# Sheet2.net
KiCad netlist of a schematic drawn in Altium Designer
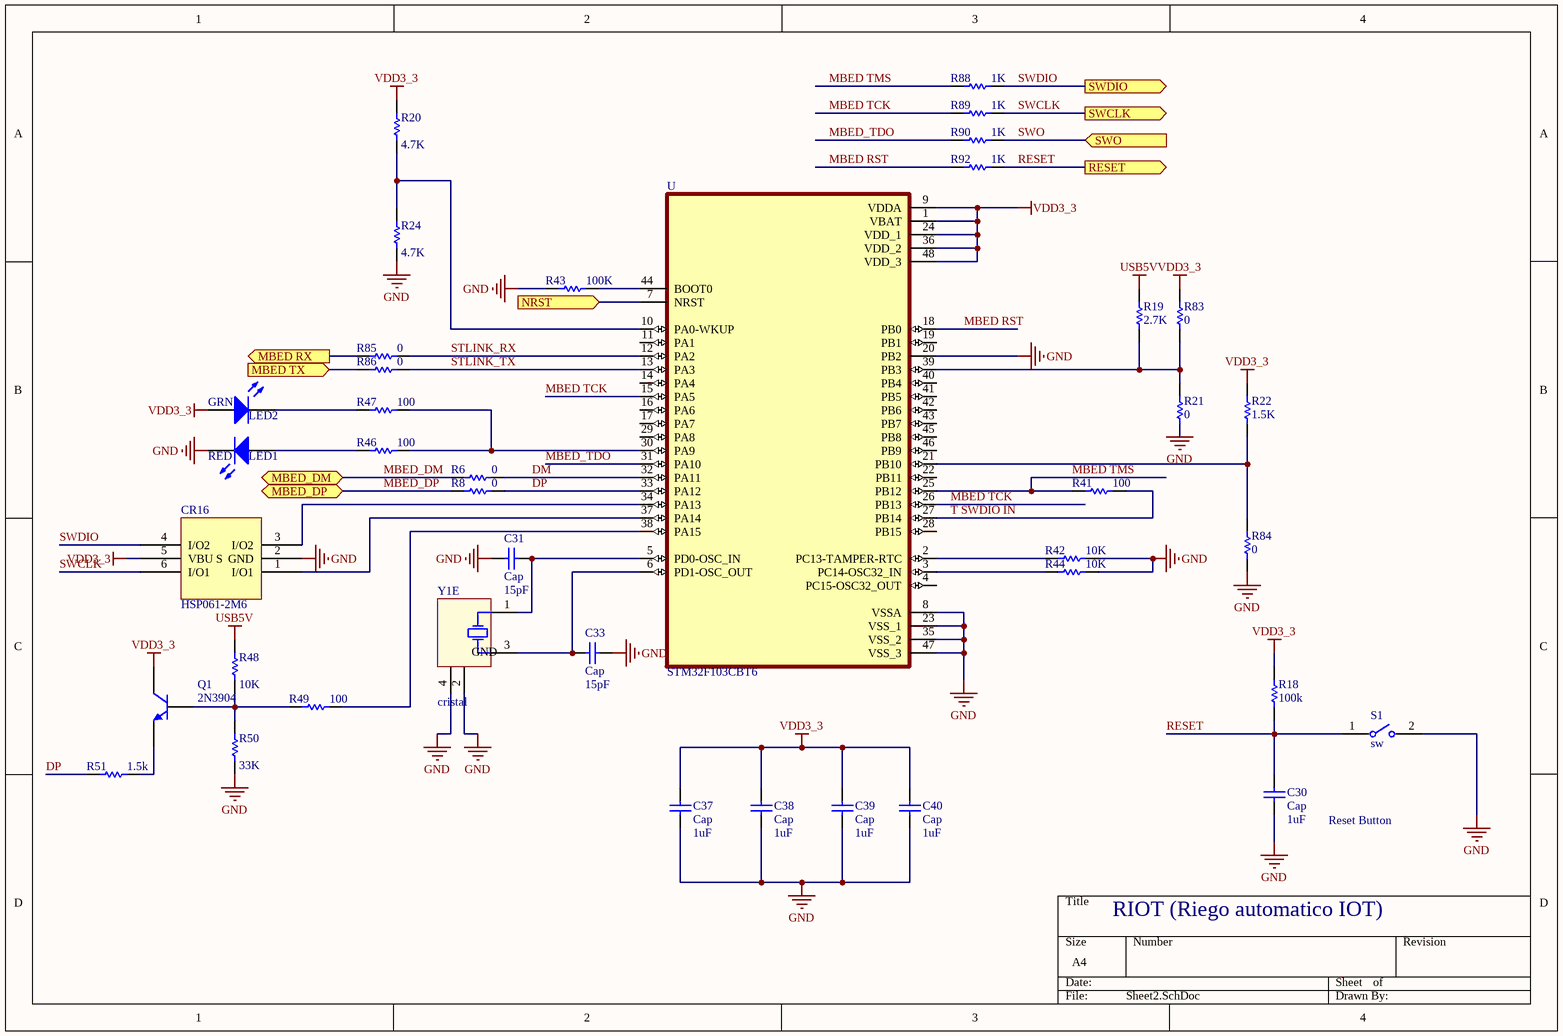
[diagram p0: Sheet2.SchDoc]

(export (version "E")
  (design (tool "Eeschema 10.0.6"))
  (components
    (comp (ref "C30")
      (value "Cap")
      (footprint "CAPC1005X35N")
      (description "Capacitor")
      (fields (field (name "ALTIUM_VALUE") "1uF") (field (name "PUBLISHER") "Altium Limited"))
      (libsource (lib "Miscellaneous Devices") (part "Cap"))
    )
    (comp (ref "C31")
      (value "Cap")
      (footprint "CAPC1005X35N")
      (description "Capacitor")
      (fields (field (name "ALTIUM_VALUE") "15pF") (field (name "PUBLISHER") "Altium Limited"))
      (libsource (lib "Miscellaneous Devices") (part "Cap"))
    )
    (comp (ref "C33")
      (value "Cap")
      (footprint "CAPC1005X35N")
      (description "Capacitor")
      (fields (field (name "ALTIUM_VALUE") "15pF") (field (name "PUBLISHER") "Altium Limited"))
      (libsource (lib "Miscellaneous Devices") (part "Cap"))
    )
    (comp (ref "C37")
      (value "Cap")
      (footprint "CAPC1005X35N")
      (description "Capacitor")
      (fields (field (name "ALTIUM_VALUE") "1uF") (field (name "PUBLISHER") "Altium Limited"))
      (libsource (lib "Miscellaneous Devices") (part "Cap"))
    )
    (comp (ref "C38")
      (value "Cap")
      (footprint "CAPC1005X35N")
      (description "Capacitor")
      (fields (field (name "ALTIUM_VALUE") "1uF") (field (name "PUBLISHER") "Altium Limited"))
      (libsource (lib "Miscellaneous Devices") (part "Cap"))
    )
    (comp (ref "C39")
      (value "Cap")
      (footprint "CAPC1005X35N")
      (description "Capacitor")
      (fields (field (name "ALTIUM_VALUE") "1uF") (field (name "PUBLISHER") "Altium Limited"))
      (libsource (lib "Miscellaneous Devices") (part "Cap"))
    )
    (comp (ref "C40")
      (value "Cap")
      (footprint "CAPC1005X35N")
      (description "Capacitor")
      (fields (field (name "ALTIUM_VALUE") "1uF") (field (name "PUBLISHER") "Altium Limited"))
      (libsource (lib "Miscellaneous Devices") (part "Cap"))
    )
    (comp (ref "CR16")
      (value "HSP061-2M6")
      (footprint "PSON40P120X130X55-6N")
      (libsource (lib "Components - 07.03.22 - 14.02") (part "HSP061-2M6"))
    )
    (comp (ref "GRN")
      (value "LED2")
      (footprint "FP-SML-P11MTT86-MFG")
      (description "Typical INFRARED GaAs LED")
      (fields (field (name "PUBLISHER") "Altium Limited"))
      (libsource (lib "Miscellaneous Devices") (part "LED0"))
    )
    (comp (ref "Q1")
      (value "2N3904")
      (footprint "TO-92A")
      (description "NPN General Purpose Amplifier")
      (fields (field (name "PUBLISHER") "Altium Limited"))
      (libsource (lib "Miscellaneous Devices") (part "2N3904"))
    )
    (comp (ref "R6")
      (value "0")
      (footprint "RESC1005X35N")
      (description "Resistor")
      (fields (field (name "Comment") "Res1") (field (name "PUBLISHER") "Altium Limited"))
      (libsource (lib "Miscellaneous Devices") (part "Res1"))
    )
    (comp (ref "R8")
      (value "0")
      (footprint "RESC1005X35N")
      (description "Resistor")
      (fields (field (name "Comment") "Res1") (field (name "PUBLISHER") "Altium Limited"))
      (libsource (lib "Miscellaneous Devices") (part "Res1"))
    )
    (comp (ref "R18")
      (value "100k")
      (footprint "RESC1005X35N")
      (description "Resistor")
      (fields (field (name "Comment") "Res1") (field (name "PUBLISHER") "Altium Limited"))
      (libsource (lib "Miscellaneous Devices") (part "Res1"))
    )
    (comp (ref "R19")
      (value "2.7K")
      (footprint "RESC1005X35N")
      (description "Resistor")
      (fields (field (name "Comment") "Res1") (field (name "PUBLISHER") "Altium Limited"))
      (libsource (lib "Miscellaneous Devices") (part "Res1"))
    )
    (comp (ref "R20")
      (value "4.7K")
      (footprint "RESC1005X35N")
      (description "Resistor")
      (fields (field (name "Comment") "Res1") (field (name "PUBLISHER") "Altium Limited"))
      (libsource (lib "Miscellaneous Devices") (part "Res1"))
    )
    (comp (ref "R21")
      (value "0")
      (footprint "RESC1005X35N")
      (description "Resistor")
      (fields (field (name "Comment") "Res1") (field (name "PUBLISHER") "Altium Limited"))
      (libsource (lib "Miscellaneous Devices") (part "Res1"))
    )
    (comp (ref "R22")
      (value "1.5K")
      (footprint "RESC1005X35N")
      (description "Resistor")
      (fields (field (name "Comment") "Res1") (field (name "PUBLISHER") "Altium Limited"))
      (libsource (lib "Miscellaneous Devices") (part "Res1"))
    )
    (comp (ref "R24")
      (value "4.7K")
      (footprint "RESC1005X35N")
      (description "Resistor")
      (fields (field (name "Comment") "Res1") (field (name "PUBLISHER") "Altium Limited"))
      (libsource (lib "Miscellaneous Devices") (part "Res1"))
    )
    (comp (ref "R41")
      (value "100")
      (footprint "RESC1005X35N")
      (description "Resistor")
      (fields (field (name "Comment") "Res1") (field (name "PUBLISHER") "Altium Limited"))
      (libsource (lib "Miscellaneous Devices") (part "Res1"))
    )
    (comp (ref "R42")
      (value "10K")
      (footprint "RESC1005X35N")
      (description "Resistor")
      (fields (field (name "Comment") "Res1") (field (name "PUBLISHER") "Altium Limited"))
      (libsource (lib "Miscellaneous Devices") (part "Res1"))
    )
    (comp (ref "R43")
      (value "100K")
      (footprint "RESC1005X35N")
      (description "Resistor")
      (fields (field (name "Comment") "Res1") (field (name "PUBLISHER") "Altium Limited"))
      (libsource (lib "Miscellaneous Devices") (part "Res1"))
    )
    (comp (ref "R44")
      (value "10K")
      (footprint "RESC1005X35N")
      (description "Resistor")
      (fields (field (name "Comment") "Res1") (field (name "PUBLISHER") "Altium Limited"))
      (libsource (lib "Miscellaneous Devices") (part "Res1"))
    )
    (comp (ref "R46")
      (value "100")
      (footprint "RESC1005X35N")
      (description "Resistor")
      (fields (field (name "Comment") "Res1") (field (name "PUBLISHER") "Altium Limited"))
      (libsource (lib "Miscellaneous Devices") (part "Res1"))
    )
    (comp (ref "R47")
      (value "100")
      (footprint "RESC1005X35N")
      (description "Resistor")
      (fields (field (name "Comment") "Res1") (field (name "PUBLISHER") "Altium Limited"))
      (libsource (lib "Miscellaneous Devices") (part "Res1"))
    )
    (comp (ref "R48")
      (value "10K")
      (footprint "RESC1005X35N")
      (description "Resistor")
      (fields (field (name "Comment") "Res1") (field (name "PUBLISHER") "Altium Limited"))
      (libsource (lib "Miscellaneous Devices") (part "Res1"))
    )
    (comp (ref "R49")
      (value "100")
      (footprint "RESC1005X35N")
      (description "Resistor")
      (fields (field (name "Comment") "Res1") (field (name "PUBLISHER") "Altium Limited"))
      (libsource (lib "Miscellaneous Devices") (part "Res1"))
    )
    (comp (ref "R50")
      (value "33K")
      (footprint "RESC1005X35N")
      (description "Resistor")
      (fields (field (name "Comment") "Res1") (field (name "PUBLISHER") "Altium Limited"))
      (libsource (lib "Miscellaneous Devices") (part "Res1"))
    )
    (comp (ref "R51")
      (value "1.5k")
      (footprint "RESC1005X35N")
      (description "Resistor")
      (fields (field (name "Comment") "Res1") (field (name "PUBLISHER") "Altium Limited"))
      (libsource (lib "Miscellaneous Devices") (part "Res1"))
    )
    (comp (ref "R83")
      (value "0")
      (footprint "RESC1005X35N")
      (description "Resistor")
      (fields (field (name "Comment") "Res1") (field (name "PUBLISHER") "Altium Limited"))
      (libsource (lib "Miscellaneous Devices") (part "Res1"))
    )
    (comp (ref "R84")
      (value "0")
      (footprint "RESC1005X35N")
      (description "Resistor")
      (fields (field (name "Comment") "Res1") (field (name "PUBLISHER") "Altium Limited"))
      (libsource (lib "Miscellaneous Devices") (part "Res1"))
    )
    (comp (ref "R85")
      (value "0")
      (footprint "RESC1005X35N")
      (description "Resistor")
      (fields (field (name "Comment") "Res1") (field (name "PUBLISHER") "Altium Limited"))
      (libsource (lib "Miscellaneous Devices") (part "Res1"))
    )
    (comp (ref "R86")
      (value "0")
      (footprint "RESC1005X35N")
      (description "Resistor")
      (fields (field (name "Comment") "Res1") (field (name "PUBLISHER") "Altium Limited"))
      (libsource (lib "Miscellaneous Devices") (part "Res1"))
    )
    (comp (ref "R88")
      (value "1K")
      (footprint "RESC1005X35N")
      (description "Resistor")
      (fields (field (name "Comment") "Res1") (field (name "PUBLISHER") "Altium Limited"))
      (libsource (lib "Miscellaneous Devices") (part "Res1"))
    )
    (comp (ref "R89")
      (value "1K")
      (footprint "RESC1005X35N")
      (description "Resistor")
      (fields (field (name "Comment") "Res1") (field (name "PUBLISHER") "Altium Limited"))
      (libsource (lib "Miscellaneous Devices") (part "Res1"))
    )
    (comp (ref "R90")
      (value "1K")
      (footprint "RESC1005X35N")
      (description "Resistor")
      (fields (field (name "Comment") "Res1") (field (name "PUBLISHER") "Altium Limited"))
      (libsource (lib "Miscellaneous Devices") (part "Res1"))
    )
    (comp (ref "R92")
      (value "1K")
      (footprint "RESC1005X35N")
      (description "Resistor")
      (fields (field (name "Comment") "Res1") (field (name "PUBLISHER") "Altium Limited"))
      (libsource (lib "Miscellaneous Devices") (part "Res1"))
    )
    (comp (ref "RED")
      (value "LED1")
      (footprint "FP-SML-P11MTT86-MFG")
      (description "Typical INFRARED GaAs LED")
      (fields (field (name "PUBLISHER") "Altium Limited"))
      (libsource (lib "Miscellaneous Devices") (part "LED0"))
    )
    (comp (ref "S1")
      (value "sw")
      (footprint "SW_B3U-1000P")
      (libsource (lib "Sistema_riego_lora") (part "sw"))
    )
    (comp (ref "U")
      (value "STM32F103CBT6")
      (footprint "Components - 07.03.22 - 14.02:STM-LQFP48_N")
      (description "ARMÂ® CortexÂ®-M3 STM32F1 Microcontroller IC 32-Bit 72MHz 128KB _128K x 8_ FLASH")
      (fields (field (name "MF") "STMicroelectronics"))
      (libsource (lib "SnapEDAsch") (part "STM32F103CBT6"))
    )
    (comp (ref "Y1")
      (value "cristal")
      (footprint "ABRA-ABMM2-4_V")
      (libsource (lib "Sistema_riego_lora") (part "cristal"))
    )
  )
  (nets
    (net (code "1") (name "/DM") (class "Default")
      (node (ref "R6") (pin "2") (pinfunction "2_2") (pintype "passive"))
      (node (ref "U") (pin "32") (pinfunction "PA11_32") (pintype "bidirectional"))
    )
    (net (code "2") (name "/DP") (class "Default")
      (node (ref "R51") (pin "1") (pinfunction "1_1") (pintype "passive"))
      (node (ref "R8") (pin "2") (pinfunction "2_2") (pintype "passive"))
      (node (ref "U") (pin "33") (pinfunction "PA12_33") (pintype "bidirectional"))
    )
    (net (code "3") (name "/MBED RST") (class "Default")
      (node (ref "R92") (pin "1") (pinfunction "1_1") (pintype "passive"))
      (node (ref "U") (pin "18") (pinfunction "PB0_18") (pintype "bidirectional"))
    )
    (net (code "4") (name "/MBED RX") (class "Default")
      (node (ref "R85") (pin "1") (pinfunction "1_1") (pintype "passive"))
    )
    (net (code "5") (name "/MBED TCK") (class "Default")
      (node (ref "R89") (pin "1") (pinfunction "1_1") (pintype "passive"))
      (node (ref "U") (pin "15") (pinfunction "PA5_15") (pintype "bidirectional"))
      (node (ref "U") (pin "26") (pinfunction "PB13_26") (pintype "bidirectional"))
    )
    (net (code "6") (name "/MBED TMS") (class "Default")
      (node (ref "R41") (pin "1") (pinfunction "1_1") (pintype "passive"))
      (node (ref "R88") (pin "1") (pinfunction "1_1") (pintype "passive"))
      (node (ref "U") (pin "25") (pinfunction "PB12_25") (pintype "bidirectional"))
    )
    (net (code "7") (name "/MBED TX") (class "Default")
      (node (ref "R86") (pin "1") (pinfunction "1_1") (pintype "passive"))
    )
    (net (code "8") (name "/MBED_DM") (class "Default")
      (node (ref "R6") (pin "1") (pinfunction "1_1") (pintype "passive"))
    )
    (net (code "9") (name "/MBED_DP") (class "Default")
      (node (ref "R8") (pin "1") (pinfunction "1_1") (pintype "passive"))
    )
    (net (code "10") (name "/MBED_TDO") (class "Default")
      (node (ref "R90") (pin "1") (pinfunction "1_1") (pintype "passive"))
      (node (ref "U") (pin "31") (pinfunction "PA10_31") (pintype "bidirectional"))
    )
    (net (code "11") (name "/NRST") (class "Default")
      (node (ref "U") (pin "7") (pinfunction "NRST_7") (pintype "passive"))
    )
    (net (code "12") (name "/RESET") (class "Default")
      (node (ref "C30") (pin "2") (pinfunction "2_2") (pintype "passive"))
      (node (ref "R18") (pin "1") (pinfunction "1_1") (pintype "passive"))
      (node (ref "R92") (pin "2") (pinfunction "2_2") (pintype "passive"))
      (node (ref "S1") (pin "1") (pinfunction "1_1") (pintype "passive"))
    )
    (net (code "13") (name "/STLINK_RX") (class "Default")
      (node (ref "R85") (pin "2") (pinfunction "2_2") (pintype "passive"))
      (node (ref "U") (pin "12") (pinfunction "PA2_12") (pintype "bidirectional"))
    )
    (net (code "14") (name "/STLINK_TX") (class "Default")
      (node (ref "R86") (pin "2") (pinfunction "2_2") (pintype "passive"))
      (node (ref "U") (pin "13") (pinfunction "PA3_13") (pintype "bidirectional"))
    )
    (net (code "15") (name "/SWCLK") (class "Default")
      (node (ref "CR16") (pin "6") (pinfunction "I/O1_6") (pintype "passive"))
      (node (ref "R89") (pin "2") (pinfunction "2_2") (pintype "passive"))
    )
    (net (code "16") (name "/SWDIO") (class "Default")
      (node (ref "CR16") (pin "4") (pinfunction "I/O2_4") (pintype "passive"))
      (node (ref "R88") (pin "2") (pinfunction "2_2") (pintype "passive"))
    )
    (net (code "17") (name "/SWO") (class "Default")
      (node (ref "R90") (pin "2") (pinfunction "2_2") (pintype "passive"))
    )
    (net (code "18") (name "/T SWDIO IN") (class "Default")
      (node (ref "R41") (pin "2") (pinfunction "2_2") (pintype "passive"))
      (node (ref "U") (pin "27") (pinfunction "PB14_27") (pintype "bidirectional"))
    )
    (net (code "19") (name "GND") (class "Default")
      (node (ref "C30") (pin "1") (pinfunction "1_1") (pintype "passive"))
      (node (ref "C31") (pin "1") (pinfunction "1_1") (pintype "passive"))
      (node (ref "C33") (pin "2") (pinfunction "2_2") (pintype "passive"))
      (node (ref "C37") (pin "1") (pinfunction "1_1") (pintype "passive"))
      (node (ref "C38") (pin "1") (pinfunction "1_1") (pintype "passive"))
      (node (ref "C39") (pin "1") (pinfunction "1_1") (pintype "passive"))
      (node (ref "C40") (pin "1") (pinfunction "1_1") (pintype "passive"))
      (node (ref "CR16") (pin "2") (pinfunction "GND_2") (pintype "passive"))
      (node (ref "R21") (pin "1") (pinfunction "1_1") (pintype "passive"))
      (node (ref "R24") (pin "1") (pinfunction "1_1") (pintype "passive"))
      (node (ref "R42") (pin "2") (pinfunction "2_2") (pintype "passive"))
      (node (ref "R43") (pin "1") (pinfunction "1_1") (pintype "passive"))
      (node (ref "R44") (pin "2") (pinfunction "2_2") (pintype "passive"))
      (node (ref "R50") (pin "1") (pinfunction "1_1") (pintype "passive"))
      (node (ref "R84") (pin "1") (pinfunction "1_1") (pintype "passive"))
      (node (ref "RED") (pin "2") (pinfunction "K_2") (pintype "passive"))
      (node (ref "S1") (pin "2") (pinfunction "2_2") (pintype "passive"))
      (node (ref "U") (pin "20") (pinfunction "PB2_20") (pintype "passive"))
      (node (ref "U") (pin "23") (pinfunction "VSS_1_23") (pintype "power_in"))
      (node (ref "U") (pin "35") (pinfunction "VSS_2_35") (pintype "power_in"))
      (node (ref "U") (pin "47") (pinfunction "VSS_3_47") (pintype "power_in"))
      (node (ref "U") (pin "8") (pinfunction "VSSA_8") (pintype "power_in"))
      (node (ref "Y1") (pin "2") (pinfunction "GND_2") (pintype "power_in"))
      (node (ref "Y1") (pin "4") (pinfunction "GND_4") (pintype "power_in"))
    )
    (net (code "20") (name "Net-(GRN-K)") (class "Default")
      (node (ref "GRN") (pin "2") (pinfunction "K_2") (pintype "passive"))
      (node (ref "R47") (pin "1") (pinfunction "1_1") (pintype "passive"))
    )
    (net (code "21") (name "Net-(Q1-B)") (class "Default")
      (node (ref "Q1") (pin "2") (pinfunction "B_2") (pintype "passive"))
      (node (ref "R48") (pin "1") (pinfunction "1_1") (pintype "passive"))
      (node (ref "R49") (pin "1") (pinfunction "1_1") (pintype "passive"))
      (node (ref "R50") (pin "2") (pinfunction "2_2") (pintype "passive"))
    )
    (net (code "22") (name "Net-(Q1-E)") (class "Default")
      (node (ref "Q1") (pin "1") (pinfunction "E_1") (pintype "passive"))
      (node (ref "R51") (pin "2") (pinfunction "2_2") (pintype "passive"))
    )
    (net (code "23") (name "Net-(RED-A)") (class "Default")
      (node (ref "R46") (pin "1") (pinfunction "1_1") (pintype "passive"))
      (node (ref "RED") (pin "1") (pinfunction "A_1") (pintype "passive"))
    )
    (net (code "24") (name "Net-(U-BOOT0)") (class "Default")
      (node (ref "R43") (pin "2") (pinfunction "2_2") (pintype "passive"))
      (node (ref "U") (pin "44") (pinfunction "BOOT0_44") (pintype "passive"))
    )
    (net (code "25") (name "Net-(U-PA0-WKUP)") (class "Default")
      (node (ref "R20") (pin "1") (pinfunction "1_1") (pintype "passive"))
      (node (ref "R24") (pin "2") (pinfunction "2_2") (pintype "passive"))
      (node (ref "U") (pin "10") (pinfunction "PA0-WKUP_10") (pintype "bidirectional"))
    )
    (net (code "26") (name "Net-(U-PA9)") (class "Default")
      (node (ref "R46") (pin "2") (pinfunction "2_2") (pintype "passive"))
      (node (ref "R47") (pin "2") (pinfunction "2_2") (pintype "passive"))
      (node (ref "U") (pin "30") (pinfunction "PA9_30") (pintype "bidirectional"))
    )
    (net (code "27") (name "Net-(U-PA13)") (class "Default")
      (node (ref "CR16") (pin "3") (pinfunction "I/O2_3") (pintype "passive"))
      (node (ref "U") (pin "34") (pinfunction "PA13_34") (pintype "bidirectional"))
    )
    (net (code "28") (name "Net-(U-PA14)") (class "Default")
      (node (ref "CR16") (pin "1") (pinfunction "I/O1_1") (pintype "passive"))
      (node (ref "U") (pin "37") (pinfunction "PA14_37") (pintype "bidirectional"))
    )
    (net (code "29") (name "Net-(U-PA15)") (class "Default")
      (node (ref "R49") (pin "2") (pinfunction "2_2") (pintype "passive"))
      (node (ref "U") (pin "38") (pinfunction "PA15_38") (pintype "bidirectional"))
    )
    (net (code "30") (name "Net-(U-PB3)") (class "Default")
      (node (ref "R19") (pin "1") (pinfunction "1_1") (pintype "passive"))
      (node (ref "R21") (pin "2") (pinfunction "2_2") (pintype "passive"))
      (node (ref "R83") (pin "1") (pinfunction "1_1") (pintype "passive"))
      (node (ref "U") (pin "39") (pinfunction "PB3_39") (pintype "bidirectional"))
    )
    (net (code "31") (name "Net-(U-PB10)") (class "Default")
      (node (ref "R22") (pin "1") (pinfunction "1_1") (pintype "passive"))
      (node (ref "R84") (pin "2") (pinfunction "2_2") (pintype "passive"))
      (node (ref "U") (pin "21") (pinfunction "PB10_21") (pintype "bidirectional"))
    )
    (net (code "32") (name "Net-(U-PC13-TAMPER-RTC)") (class "Default")
      (node (ref "R42") (pin "1") (pinfunction "1_1") (pintype "passive"))
      (node (ref "U") (pin "2") (pinfunction "PC13-TAMPER-RTC_2") (pintype "bidirectional"))
    )
    (net (code "33") (name "Net-(U-PC14-OSC32_IN)") (class "Default")
      (node (ref "R44") (pin "1") (pinfunction "1_1") (pintype "passive"))
      (node (ref "U") (pin "3") (pinfunction "PC14-OSC32_IN_3") (pintype "bidirectional"))
    )
    (net (code "34") (name "Net-(U-PD0-OSC_IN)") (class "Default")
      (node (ref "C31") (pin "2") (pinfunction "2_2") (pintype "passive"))
      (node (ref "U") (pin "5") (pinfunction "PD0-OSC_IN_5") (pintype "bidirectional"))
      (node (ref "Y1") (pin "1") (pinfunction "X1_1") (pintype "passive"))
    )
    (net (code "35") (name "Net-(U-PD1-OSC_OUT)") (class "Default")
      (node (ref "C33") (pin "1") (pinfunction "1_1") (pintype "passive"))
      (node (ref "U") (pin "6") (pinfunction "PD1-OSC_OUT_6") (pintype "bidirectional"))
      (node (ref "Y1") (pin "3") (pinfunction "X2_3") (pintype "passive"))
    )
    (net (code "36") (name "USB5V") (class "Default")
      (node (ref "R19") (pin "2") (pinfunction "2_2") (pintype "passive"))
      (node (ref "R48") (pin "2") (pinfunction "2_2") (pintype "passive"))
    )
    (net (code "37") (name "VDD3_3") (class "Default")
      (node (ref "C37") (pin "2") (pinfunction "2_2") (pintype "passive"))
      (node (ref "C38") (pin "2") (pinfunction "2_2") (pintype "passive"))
      (node (ref "C39") (pin "2") (pinfunction "2_2") (pintype "passive"))
      (node (ref "C40") (pin "2") (pinfunction "2_2") (pintype "passive"))
      (node (ref "CR16") (pin "5") (pinfunction "VBU_S_5") (pintype "passive"))
      (node (ref "GRN") (pin "1") (pinfunction "A_1") (pintype "passive"))
      (node (ref "Q1") (pin "3") (pinfunction "C_3") (pintype "passive"))
      (node (ref "R18") (pin "2") (pinfunction "2_2") (pintype "passive"))
      (node (ref "R20") (pin "2") (pinfunction "2_2") (pintype "passive"))
      (node (ref "R22") (pin "2") (pinfunction "2_2") (pintype "passive"))
      (node (ref "R83") (pin "2") (pinfunction "2_2") (pintype "passive"))
      (node (ref "U") (pin "1") (pinfunction "VBAT_1") (pintype "power_in"))
      (node (ref "U") (pin "24") (pinfunction "VDD_1_24") (pintype "power_in"))
      (node (ref "U") (pin "36") (pinfunction "VDD_2_36") (pintype "power_in"))
      (node (ref "U") (pin "48") (pinfunction "VDD_3_48") (pintype "power_in"))
      (node (ref "U") (pin "9") (pinfunction "VDDA_9") (pintype "power_in"))
    )
    (net (code "38") (name "unconnected-(U-PA1-Pad11)") (class "Default")
      (node (ref "U") (pin "11") (pinfunction "PA1_11") (pintype "bidirectional"))
    )
    (net (code "39") (name "unconnected-(U-PA4-Pad14)") (class "Default")
      (node (ref "U") (pin "14") (pinfunction "PA4_14") (pintype "bidirectional"))
    )
    (net (code "40") (name "unconnected-(U-PA6-Pad16)") (class "Default")
      (node (ref "U") (pin "16") (pinfunction "PA6_16") (pintype "bidirectional"))
    )
    (net (code "41") (name "unconnected-(U-PA7-Pad17)") (class "Default")
      (node (ref "U") (pin "17") (pinfunction "PA7_17") (pintype "bidirectional"))
    )
    (net (code "42") (name "unconnected-(U-PA8-Pad29)") (class "Default")
      (node (ref "U") (pin "29") (pinfunction "PA8_29") (pintype "bidirectional"))
    )
    (net (code "43") (name "unconnected-(U-PB1-Pad19)") (class "Default")
      (node (ref "U") (pin "19") (pinfunction "PB1_19") (pintype "bidirectional"))
    )
    (net (code "44") (name "unconnected-(U-PB4-Pad40)") (class "Default")
      (node (ref "U") (pin "40") (pinfunction "PB4_40") (pintype "bidirectional"))
    )
    (net (code "45") (name "unconnected-(U-PB5-Pad41)") (class "Default")
      (node (ref "U") (pin "41") (pinfunction "PB5_41") (pintype "bidirectional"))
    )
    (net (code "46") (name "unconnected-(U-PB6-Pad42)") (class "Default")
      (node (ref "U") (pin "42") (pinfunction "PB6_42") (pintype "bidirectional"))
    )
    (net (code "47") (name "unconnected-(U-PB7-Pad43)") (class "Default")
      (node (ref "U") (pin "43") (pinfunction "PB7_43") (pintype "bidirectional"))
    )
    (net (code "48") (name "unconnected-(U-PB8-Pad45)") (class "Default")
      (node (ref "U") (pin "45") (pinfunction "PB8_45") (pintype "bidirectional"))
    )
    (net (code "49") (name "unconnected-(U-PB9-Pad46)") (class "Default")
      (node (ref "U") (pin "46") (pinfunction "PB9_46") (pintype "bidirectional"))
    )
    (net (code "50") (name "unconnected-(U-PB11-Pad22)") (class "Default")
      (node (ref "U") (pin "22") (pinfunction "PB11_22") (pintype "bidirectional"))
    )
    (net (code "51") (name "unconnected-(U-PB15-Pad28)") (class "Default")
      (node (ref "U") (pin "28") (pinfunction "PB15_28") (pintype "bidirectional"))
    )
    (net (code "52") (name "unconnected-(U-PC15-OSC32_OUT-Pad4)") (class "Default")
      (node (ref "U") (pin "4") (pinfunction "PC15-OSC32_OUT_4") (pintype "bidirectional"))
    )
  )
)
